# BATT_INPUT_TEST_BED.net
KiCad netlist of a schematic drawn in EAGLE
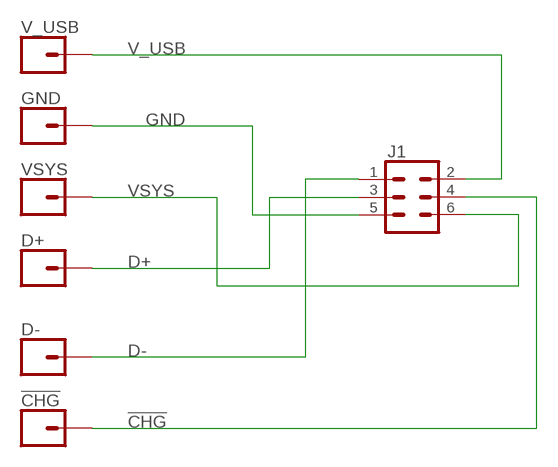
[diagram p0: schematic, sheet 1]

(export (version "E")
  (design (tool "Eeschema 10.0.6"))
  (components
    (comp (ref "!CHG!")
      (value "CONN_01POGOPIN_HOLE_LARGE")
      (footprint "eagle-import:1X01_POGOPIN_HOLE_0.061_DIA")
      (libsource (lib "eagle-import") (part "CONN_01POGOPIN_HOLE_LARGE"))
    )
    (comp (ref "D+")
      (value "CONN_01POGOPIN_HOLE_LARGE")
      (footprint "eagle-import:1X01_POGOPIN_HOLE_0.061_DIA")
      (libsource (lib "eagle-import") (part "CONN_01POGOPIN_HOLE_LARGE"))
    )
    (comp (ref "D-")
      (value "CONN_01POGOPIN_HOLE_LARGE")
      (footprint "eagle-import:1X01_POGOPIN_HOLE_0.061_DIA")
      (libsource (lib "eagle-import") (part "CONN_01POGOPIN_HOLE_LARGE"))
    )
    (comp (ref "GND")
      (value "CONN_01POGOPIN_HOLE_LARGE")
      (footprint "eagle-import:1X01_POGOPIN_HOLE_0.061_DIA")
      (libsource (lib "eagle-import") (part "CONN_01POGOPIN_HOLE_LARGE"))
    )
    (comp (ref "J1")
      (value "CONN_03X22X3_SILK_MALE_PTH")
      (footprint "eagle-import:2X3")
      (libsource (lib "eagle-import") (part "CONN_03X22X3_SILK_MALE_PTH"))
    )
    (comp (ref "VSYS")
      (value "CONN_01POGOPIN_HOLE_LARGE")
      (footprint "eagle-import:1X01_POGOPIN_HOLE_0.061_DIA")
      (libsource (lib "eagle-import") (part "CONN_01POGOPIN_HOLE_LARGE"))
    )
    (comp (ref "V_USB")
      (value "CONN_01POGOPIN_HOLE_LARGE")
      (footprint "eagle-import:1X01_POGOPIN_HOLE_0.061_DIA")
      (libsource (lib "eagle-import") (part "CONN_01POGOPIN_HOLE_LARGE"))
    )
  )
  (nets
    (net (code "1") (name "/D+") (class "Default")
      (node (ref "D+") (pin "2") (pinfunction "1_2") (pintype "passive"))
      (node (ref "J1") (pin "3") (pinfunction "3_3") (pintype "bidirectional"))
    )
    (net (code "2") (name "/D-") (class "Default")
      (node (ref "D-") (pin "2") (pinfunction "1_2") (pintype "passive"))
      (node (ref "J1") (pin "1") (pinfunction "1_1") (pintype "bidirectional"))
    )
    (net (code "3") (name "/GND") (class "Default")
      (node (ref "GND") (pin "2") (pinfunction "1_2") (pintype "passive"))
      (node (ref "J1") (pin "5") (pinfunction "5_5") (pintype "bidirectional"))
    )
    (net (code "4") (name "/VSYS") (class "Default")
      (node (ref "J1") (pin "6") (pinfunction "6_6") (pintype "bidirectional"))
      (node (ref "VSYS") (pin "2") (pinfunction "1_2") (pintype "passive"))
    )
    (net (code "5") (name "/V_USB") (class "Default")
      (node (ref "J1") (pin "2") (pinfunction "2_2") (pintype "bidirectional"))
      (node (ref "V_USB") (pin "2") (pinfunction "1_2") (pintype "passive"))
    )
    (net (code "6") (name "/~{CHG}") (class "Default")
      (node (ref "!CHG!") (pin "2") (pinfunction "1_2") (pintype "passive"))
      (node (ref "J1") (pin "4") (pinfunction "4_4") (pintype "bidirectional"))
    )
  )
)
